# SSTuino_Evo.net
KiCad netlist of a schematic drawn in EAGLE
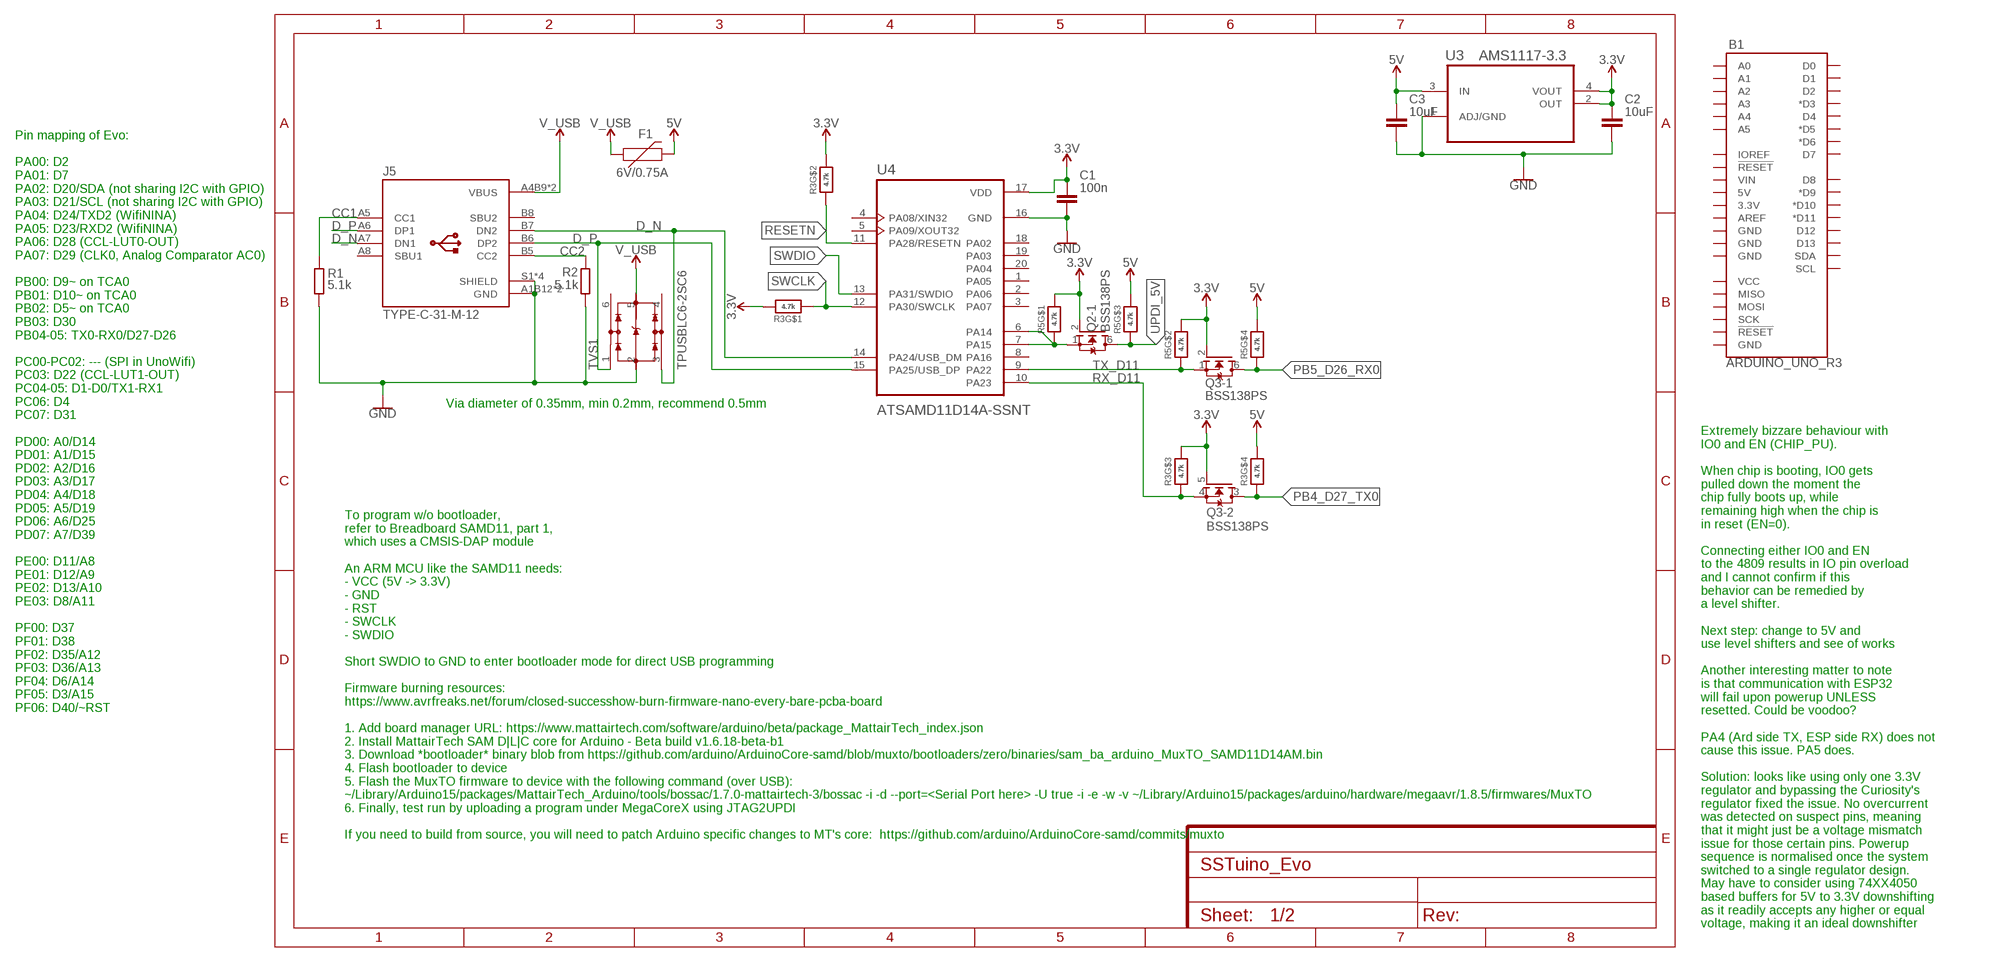
[diagram p0: schematic, sheet 1]
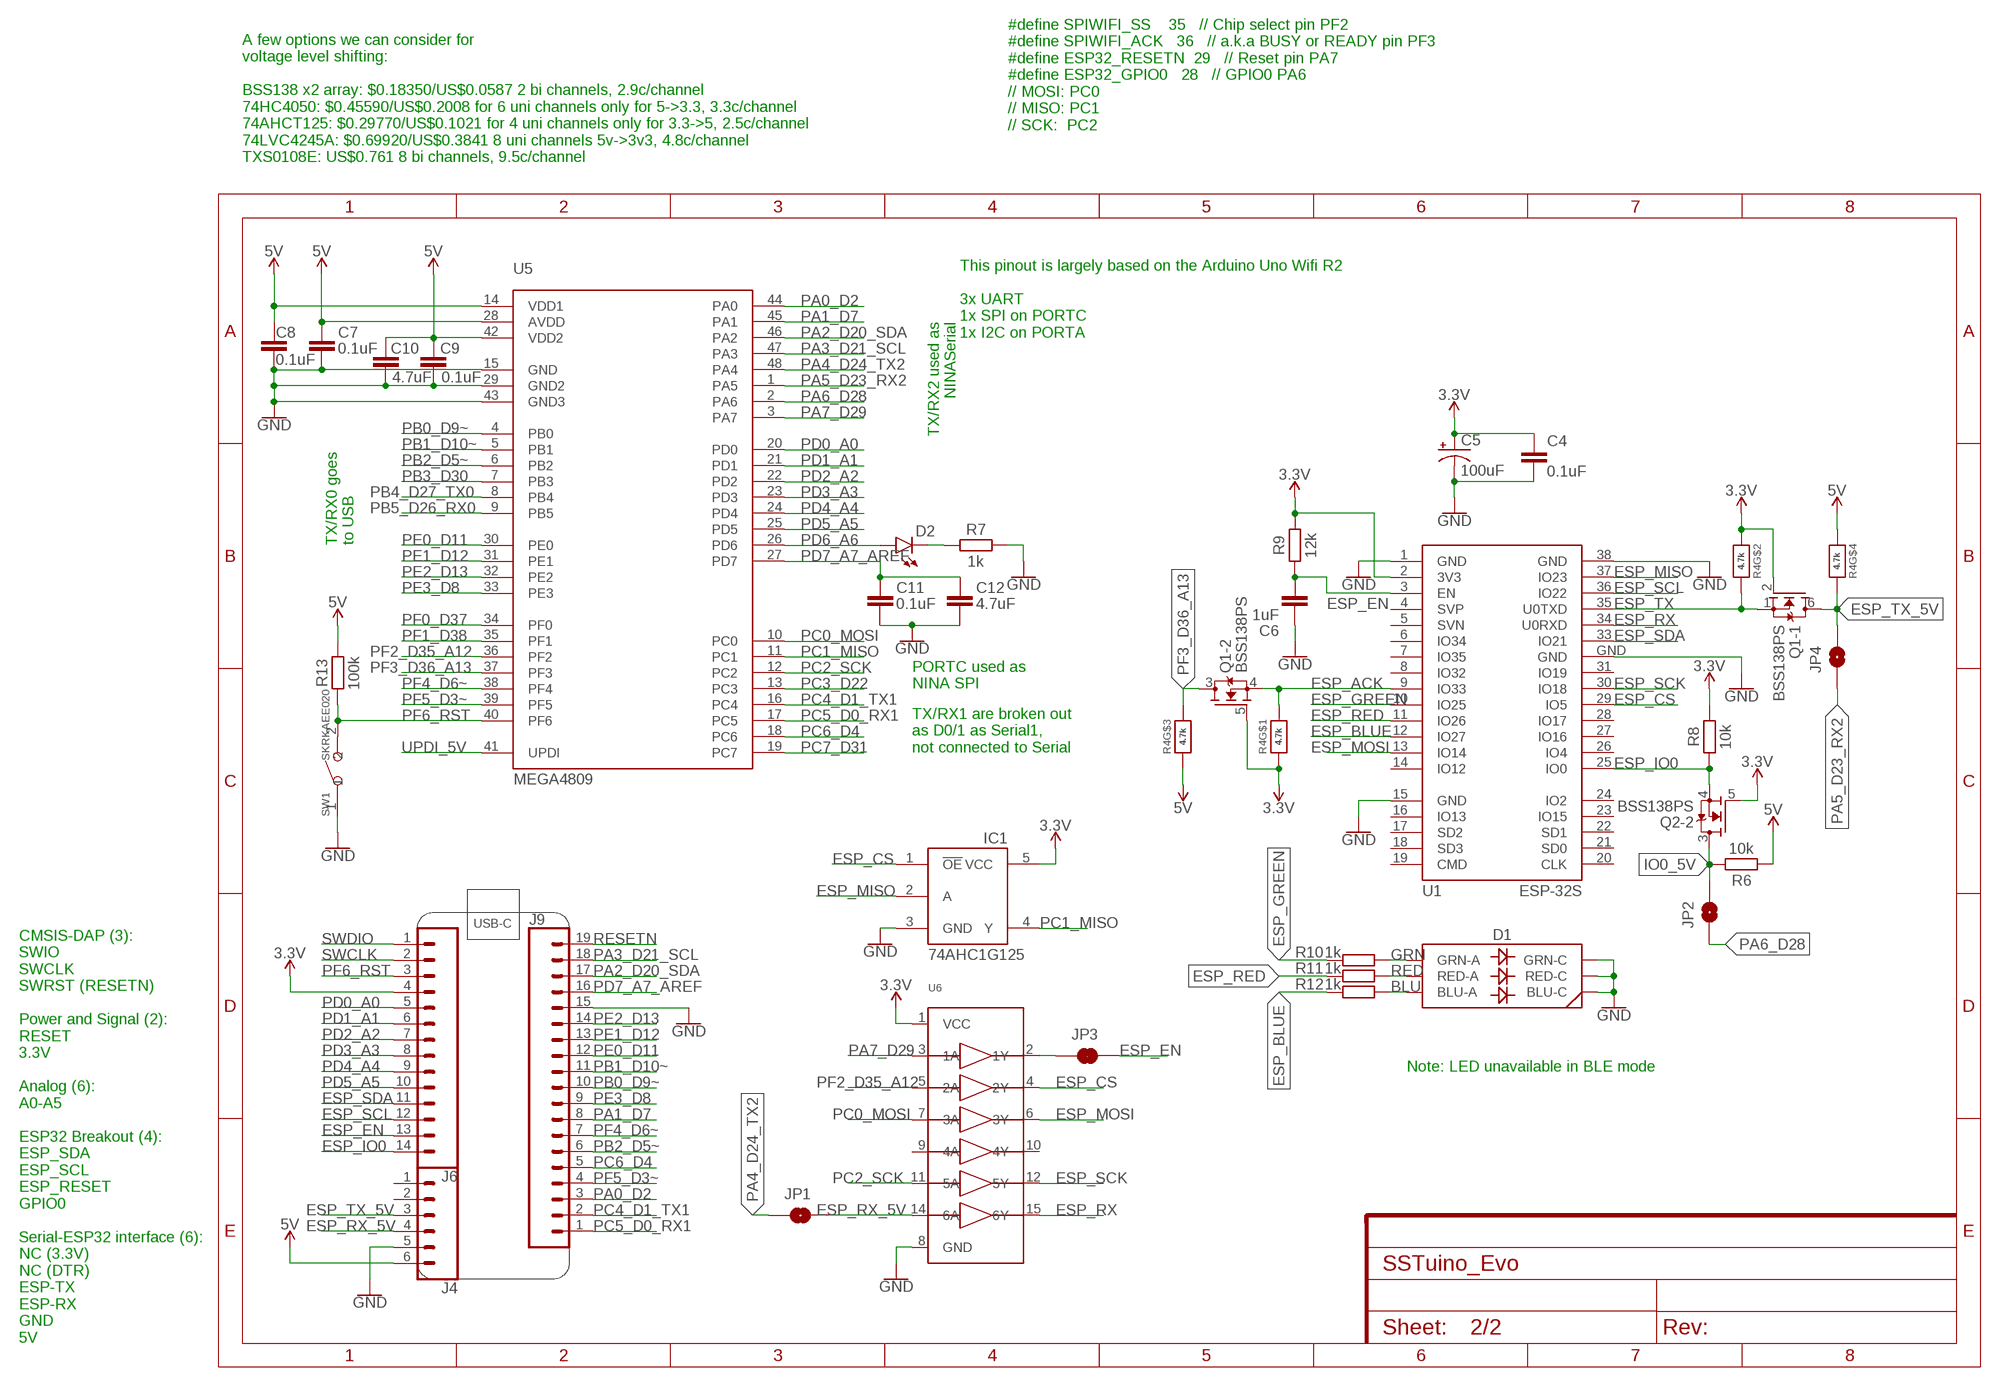
[diagram p1: schematic, sheet 2]

(export (version "E")
  (design (tool "Eeschema 10.0.6"))
  (components
    (comp (ref "B1")
      (value "ARDUINO_UNO_R3")
      (footprint "eagle-import:ARDUINO_R3")
      (libsource (lib "eagle-import") (part "ARDUINO_UNO_R3"))
    )
    (comp (ref "C1")
      (value "100n")
      (footprint "eagle-import:CAPC1005X60")
      (libsource (lib "eagle-import") (part "CCHIP-0402(1005-METRIC)_"))
    )
    (comp (ref "C2")
      (value "10uF")
      (footprint "eagle-import:CAPC1608X85")
      (libsource (lib "eagle-import") (part "CCHIP-0603(1608-METRIC)_"))
    )
    (comp (ref "C3")
      (value "10uF")
      (footprint "eagle-import:CAPC1608X85")
      (libsource (lib "eagle-import") (part "CCHIP-0603(1608-METRIC)_"))
    )
    (comp (ref "F1")
      (value "6V/0.75A")
      (footprint "eagle-import:1206")
      (fields (field (name "LCSC_PART") "C99563"))
      (libsource (lib "eagle-import") (part "PPTC_THREE-QUARTER-AMP"))
    )
    (comp (ref "J5")
      (value "TYPE-C-31-M-12")
      (footprint "eagle-import:HRO_TYPE-C-31-M-12")
      (fields (field (name "MF") "HRO Electronics Co., Ltd.") (field (name "LCSC_PART") "C165948"))
      (libsource (lib "eagle-import") (part "TYPE-C-31-M-12"))
    )
    (comp (ref "Q2")
      (value "BSS138PS")
      (footprint "eagle-import:ARDUINO-TRANSISTORS_SOT363")
      (fields (field (name "MANUFACTURER") "NXP") (field (name "LCSC_PART") "C193381"))
      (libsource (lib "eagle-import") (part "BSS138PS"))
    )
    (comp (ref "Q3")
      (value "BSS138PS")
      (footprint "eagle-import:ARDUINO-TRANSISTORS_SOT363")
      (fields (field (name "MANUFACTURER") "NXP") (field (name "LCSC_PART") "C193381"))
      (libsource (lib "eagle-import") (part "BSS138PS"))
    )
    (comp (ref "R1")
      (value "5.1k")
      (footprint "eagle-import:RESC1005X40")
      (libsource (lib "eagle-import") (part "RCHIP-0402(1005-METRIC)_"))
    )
    (comp (ref "R2")
      (value "5.1k")
      (footprint "eagle-import:RESC1005X40")
      (libsource (lib "eagle-import") (part "RCHIP-0402(1005-METRIC)_"))
    )
    (comp (ref "R3")
      (value "4.7k")
      (footprint "eagle-import:RESPACK_4X0402")
      (fields (field (name "LCSC_PART") "C1980"))
      (libsource (lib "eagle-import") (part "RESISTOR_4PACK0402"))
    )
    (comp (ref "R5")
      (value "4.7k")
      (footprint "eagle-import:RESPACK_4X0402")
      (fields (field (name "LCSC_PART") "C1980"))
      (libsource (lib "eagle-import") (part "RESISTOR_4PACK0402"))
    )
    (comp (ref "TVS1")
      (value "TPUSBLC6-2SC6")
      (footprint "eagle-import:SOT95P280X110-6N")
      (fields (field (name "LCSC_PART") "C558442"))
      (libsource (lib "eagle-import") (part "TPUSBLC6-2SC6"))
    )
    (comp (ref "U3")
      (value "AMS1117-3.3")
      (footprint "eagle-import:SOT230P696X180-4N")
      (fields (field (name "MPN") "LM1117MP-3.3") (field (name "LCSC_PART") "C6186"))
      (libsource (lib "eagle-import") (part "LM1117MP-3.3"))
    )
    (comp (ref "U4")
      (value "ATSAMD11D14A-SSNT")
      (footprint "eagle-import:SOIC127P1030X265-20N")
      (fields (field (name "MF") "Microchip") (field (name "LCSC_PART") "C2053599"))
      (libsource (lib "eagle-import") (part "ATSAMD11D14A-SSNT"))
    )
    (comp (ref "C4")
      (value "0.1uF")
      (footprint "eagle-import:CAPC1005X60")
      (libsource (lib "eagle-import") (part "CCHIP-0402(1005-METRIC)_"))
    )
    (comp (ref "C5")
      (value "100uF")
      (footprint "eagle-import:CAPMP3216X180N")
      (libsource (lib "eagle-import") (part "C-POL-USTANTALUM-1206(3216-METRIC)_"))
    )
    (comp (ref "C6")
      (value "1uF")
      (footprint "eagle-import:CAPC1005X60")
      (libsource (lib "eagle-import") (part "CCHIP-0402(1005-METRIC)_"))
    )
    (comp (ref "C7")
      (value "0.1uF")
      (footprint "eagle-import:CAPC1005X60")
      (libsource (lib "eagle-import") (part "CCHIP-0402(1005-METRIC)_"))
    )
    (comp (ref "C8")
      (value "0.1uF")
      (footprint "eagle-import:CAPC1005X60")
      (libsource (lib "eagle-import") (part "CCHIP-0402(1005-METRIC)_"))
    )
    (comp (ref "C9")
      (value "0.1uF")
      (footprint "eagle-import:CAPC1005X60")
      (libsource (lib "eagle-import") (part "CCHIP-0402(1005-METRIC)_"))
    )
    (comp (ref "C10")
      (value "4.7uF")
      (footprint "eagle-import:CAPC1005X60")
      (libsource (lib "eagle-import") (part "CCHIP-0402(1005-METRIC)_"))
    )
    (comp (ref "C11")
      (value "0.1uF")
      (footprint "eagle-import:CAPC1005X60")
      (libsource (lib "eagle-import") (part "CCHIP-0402(1005-METRIC)_"))
    )
    (comp (ref "C12")
      (value "4.7uF")
      (footprint "eagle-import:CAPC1005X60")
      (libsource (lib "eagle-import") (part "CCHIP-0402(1005-METRIC)_"))
    )
    (comp (ref "D1")
      (value "LED-RGBTC5050RGBF08")
      (footprint "eagle-import:LED-TRICOLOR-5050")
      (libsource (lib "eagle-import") (part "LED-RGBTC5050RGBF08"))
    )
    (comp (ref "D2")
      (value "LED0603")
      (footprint "eagle-import:LED-0603")
      (libsource (lib "eagle-import") (part "LED0603"))
    )
    (comp (ref "IC1")
      (value "74AHC1G125")
      (footprint "eagle-import:SOT23-5L")
      (fields (field (name "LCSC_PART") "C124295"))
      (libsource (lib "eagle-import") (part "74AHC1G125"))
    )
    (comp (ref "J4")
      (value "CONN_06NO_SILK_FEMALE_PTH")
      (footprint "eagle-import:1X06_NO_SILK")
      (libsource (lib "eagle-import") (part "CONN_06NO_SILK_FEMALE_PTH"))
    )
    (comp (ref "J6")
      (value "CONN_14NO_SILK")
      (footprint "eagle-import:1X14_NO_SILK")
      (libsource (lib "eagle-import") (part "CONN_14NO_SILK"))
    )
    (comp (ref "J9")
      (value "CONN_191X19_NO_SILK")
      (footprint "eagle-import:1X19_NO_SILK")
      (libsource (lib "eagle-import") (part "CONN_191X19_NO_SILK"))
    )
    (comp (ref "JP1")
      (value "JUMPER-SMT_2_NO_SILK")
      (footprint "eagle-import:SMT-JUMPER_2_NO_SILK")
      (libsource (lib "eagle-import") (part "JUMPER-SMT_2_NO_SILK"))
    )
    (comp (ref "JP2")
      (value "JUMPER-SMT_2_NO_SILK")
      (footprint "eagle-import:SMT-JUMPER_2_NO_SILK")
      (libsource (lib "eagle-import") (part "JUMPER-SMT_2_NO_SILK"))
    )
    (comp (ref "JP3")
      (value "JUMPER-SMT_2_NC_TRACE_SILK")
      (footprint "eagle-import:SMT-JUMPER_2_NC_TRACE_SILK")
      (libsource (lib "eagle-import") (part "JUMPER-SMT_2_NC_TRACE_SILK"))
    )
    (comp (ref "JP4")
      (value "JUMPER-SMT_2_NO_SILK")
      (footprint "eagle-import:SMT-JUMPER_2_NO_SILK")
      (libsource (lib "eagle-import") (part "JUMPER-SMT_2_NO_SILK"))
    )
    (comp (ref "Q1")
      (value "BSS138PS")
      (footprint "eagle-import:ARDUINO-TRANSISTORS_SOT363")
      (fields (field (name "MANUFACTURER") "NXP") (field (name "LCSC_PART") "C193381"))
      (libsource (lib "eagle-import") (part "BSS138PS"))
    )
    (comp (ref "R4")
      (value "4.7k")
      (footprint "eagle-import:RESPACK_4X0402")
      (fields (field (name "LCSC_PART") "C1980"))
      (libsource (lib "eagle-import") (part "RESISTOR_4PACK0402"))
    )
    (comp (ref "R6")
      (value "10k")
      (footprint "eagle-import:RESC1005X40")
      (libsource (lib "eagle-import") (part "RCHIP-0402(1005-METRIC)_"))
    )
    (comp (ref "R7")
      (value "1k")
      (footprint "eagle-import:RESC1005X40")
      (libsource (lib "eagle-import") (part "RCHIP-0402(1005-METRIC)_"))
    )
    (comp (ref "R8")
      (value "10k")
      (footprint "eagle-import:RESC1005X40")
      (libsource (lib "eagle-import") (part "RCHIP-0402(1005-METRIC)_"))
    )
    (comp (ref "R9")
      (value "12k")
      (footprint "eagle-import:RESC1005X40")
      (libsource (lib "eagle-import") (part "RCHIP-0402(1005-METRIC)_"))
    )
    (comp (ref "R10")
      (value "1k")
      (footprint "eagle-import:RESC1005X40")
      (libsource (lib "eagle-import") (part "RCHIP-0402(1005-METRIC)_"))
    )
    (comp (ref "R11")
      (value "1k")
      (footprint "eagle-import:RESC1005X40")
      (libsource (lib "eagle-import") (part "RCHIP-0402(1005-METRIC)_"))
    )
    (comp (ref "R12")
      (value "1k")
      (footprint "eagle-import:RESC1005X40")
      (libsource (lib "eagle-import") (part "RCHIP-0402(1005-METRIC)_"))
    )
    (comp (ref "R13")
      (value "100k")
      (footprint "eagle-import:RESC1005X40")
      (libsource (lib "eagle-import") (part "RCHIP-0402(1005-METRIC)_"))
    )
    (comp (ref "SW1")
      (value "SKRKAEE020")
      (footprint "eagle-import:SW2-2.6-3.9X2.9X1.5+0.4MM")
      (fields (field (name "LCSC_PART") "C115357") (field (name "LCSC_PART_1") "C115357"))
      (libsource (lib "eagle-import") (part "SMD-BUTTON(2P-3.9X2.9X1.5+0.4MM)-SKRKAEE020"))
    )
    (comp (ref "U1")
      (value "ESP-32S")
      (footprint "eagle-import:ESP-32S")
      (libsource (lib "eagle-import") (part "ESP-32S"))
    )
    (comp (ref "U5")
      (value "MEGA4809")
      (footprint "eagle-import:TQFP48")
      (fields (field (name "LCSC_PART") "C189475"))
      (libsource (lib "eagle-import") (part "MEGA4809"))
    )
    (comp (ref "U6")
      (value "74HC4050DTSSOP")
      (footprint "eagle-import:TSSOP16")
      (fields (field (name "LCSC_PART") "C43181"))
      (libsource (lib "eagle-import") (part "74HC4050DTSSOP"))
    )
  )
  (nets
    (net (code "1") (name "3.3V") (class "Default")
      (node (ref "C1") (pin "1") (pinfunction "1_1") (pintype "passive"))
      (node (ref "C2") (pin "1") (pinfunction "1_1") (pintype "passive"))
      (node (ref "C4") (pin "1") (pinfunction "1_1") (pintype "passive"))
      (node (ref "C5") (pin "1") (pinfunction "+_1") (pintype "passive"))
      (node (ref "IC1") (pin "5") (pinfunction "VCC_5") (pintype "power_in"))
      (node (ref "J6") (pin "4") (pinfunction "4_4") (pintype "passive"))
      (node (ref "Q1") (pin "2") (pinfunction "G_2") (pintype "passive"))
      (node (ref "Q1") (pin "5") (pinfunction "G_5") (pintype "passive"))
      (node (ref "Q2") (pin "2") (pinfunction "G_2") (pintype "passive"))
      (node (ref "Q2") (pin "5") (pinfunction "G_5") (pintype "passive"))
      (node (ref "Q3") (pin "2") (pinfunction "G_2") (pintype "passive"))
      (node (ref "Q3") (pin "5") (pinfunction "G_5") (pintype "passive"))
      (node (ref "R3") (pin "6") (pinfunction "2_6") (pintype "passive"))
      (node (ref "R3") (pin "7") (pinfunction "2_7") (pintype "passive"))
      (node (ref "R3") (pin "8") (pinfunction "2_8") (pintype "passive"))
      (node (ref "R4") (pin "1") (pinfunction "1_1") (pintype "passive"))
      (node (ref "R4") (pin "2") (pinfunction "1_2") (pintype "passive"))
      (node (ref "R5") (pin "7") (pinfunction "2_7") (pintype "passive"))
      (node (ref "R5") (pin "8") (pinfunction "2_8") (pintype "passive"))
      (node (ref "R8") (pin "2") (pinfunction "2_2") (pintype "passive"))
      (node (ref "R9") (pin "2") (pinfunction "2_2") (pintype "passive"))
      (node (ref "U1") (pin "2") (pinfunction "3V3_2") (pintype "power_in"))
      (node (ref "U3") (pin "2") (pinfunction "OUT_2") (pintype "output"))
      (node (ref "U3") (pin "4") (pinfunction "VOUT_4") (pintype "output"))
      (node (ref "U4") (pin "17") (pinfunction "VDD_17") (pintype "power_in"))
      (node (ref "U6") (pin "1") (pinfunction "VCC_1") (pintype "bidirectional"))
    )
    (net (code "2") (name "5V") (class "Default")
      (node (ref "C10") (pin "1") (pinfunction "1_1") (pintype "passive"))
      (node (ref "C3") (pin "1") (pinfunction "1_1") (pintype "passive"))
      (node (ref "C7") (pin "1") (pinfunction "1_1") (pintype "passive"))
      (node (ref "C8") (pin "1") (pinfunction "1_1") (pintype "passive"))
      (node (ref "C9") (pin "1") (pinfunction "1_1") (pintype "passive"))
      (node (ref "F1") (pin "2") (pinfunction "2_2") (pintype "bidirectional"))
      (node (ref "J4") (pin "6") (pinfunction "6_6") (pintype "passive"))
      (node (ref "R13") (pin "2") (pinfunction "2_2") (pintype "passive"))
      (node (ref "R3") (pin "5") (pinfunction "2_5") (pintype "passive"))
      (node (ref "R4") (pin "3") (pinfunction "1_3") (pintype "passive"))
      (node (ref "R4") (pin "4") (pinfunction "1_4") (pintype "passive"))
      (node (ref "R5") (pin "5") (pinfunction "2_5") (pintype "passive"))
      (node (ref "R5") (pin "6") (pinfunction "2_6") (pintype "passive"))
      (node (ref "R6") (pin "1") (pinfunction "1_1") (pintype "passive"))
      (node (ref "U3") (pin "3") (pinfunction "IN_3") (pintype "input"))
      (node (ref "U5") (pin "14") (pinfunction "VDD1_14") (pintype "bidirectional"))
      (node (ref "U5") (pin "28") (pinfunction "AVDD_28") (pintype "bidirectional"))
      (node (ref "U5") (pin "42") (pinfunction "VDD2_42") (pintype "bidirectional"))
    )
    (net (code "3") (name "BLU") (class "Default")
      (node (ref "D1") (pin "6") (pinfunction "BLU-A_6") (pintype "bidirectional"))
      (node (ref "R12") (pin "2") (pinfunction "2_2") (pintype "passive"))
    )
    (net (code "4") (name "CC1") (class "Default")
      (node (ref "J5") (pin "A5") (pinfunction "CC1_A5") (pintype "bidirectional"))
      (node (ref "R1") (pin "1") (pinfunction "1_1") (pintype "passive"))
    )
    (net (code "5") (name "CC2") (class "Default")
      (node (ref "J5") (pin "B5") (pinfunction "CC2_B5") (pintype "bidirectional"))
      (node (ref "R2") (pin "2") (pinfunction "2_2") (pintype "passive"))
    )
    (net (code "6") (name "D_N") (class "Default")
      (node (ref "J5") (pin "A7") (pinfunction "DN1_A7") (pintype "bidirectional"))
      (node (ref "J5") (pin "B7") (pinfunction "DN2_B7") (pintype "bidirectional"))
      (node (ref "TVS1") (pin "3") (pinfunction "IO2_3") (pintype "passive"))
      (node (ref "U4") (pin "14") (pinfunction "PA24/USB_DM_14") (pintype "bidirectional"))
    )
    (net (code "7") (name "D_P") (class "Default")
      (node (ref "J5") (pin "A6") (pinfunction "DP1_A6") (pintype "bidirectional"))
      (node (ref "J5") (pin "B6") (pinfunction "DP2_B6") (pintype "bidirectional"))
      (node (ref "TVS1") (pin "1") (pinfunction "IO1_1") (pintype "passive"))
      (node (ref "U4") (pin "15") (pinfunction "PA25/USB_DP_15") (pintype "bidirectional"))
    )
    (net (code "8") (name "ESP_ACK") (class "Default")
      (node (ref "Q1") (pin "4") (pinfunction "S_4") (pintype "passive"))
      (node (ref "R4") (pin "8") (pinfunction "2_8") (pintype "passive"))
      (node (ref "U1") (pin "9") (pinfunction "IO33_9") (pintype "bidirectional"))
    )
    (net (code "9") (name "ESP_BLUE") (class "Default")
      (node (ref "R12") (pin "1") (pinfunction "1_1") (pintype "passive"))
      (node (ref "U1") (pin "12") (pinfunction "IO27_12") (pintype "bidirectional"))
    )
    (net (code "10") (name "ESP_CS") (class "Default")
      (node (ref "IC1") (pin "1") (pinfunction "~{OE}_1") (pintype "input"))
      (node (ref "U1") (pin "29") (pinfunction "IO5_29") (pintype "bidirectional"))
      (node (ref "U6") (pin "4") (pinfunction "2Y_4") (pintype "bidirectional"))
    )
    (net (code "11") (name "ESP_EN") (class "Default")
      (node (ref "C6") (pin "2") (pinfunction "2_2") (pintype "passive"))
      (node (ref "J6") (pin "13") (pinfunction "13_13") (pintype "passive"))
      (node (ref "JP3") (pin "2") (pinfunction "2_2") (pintype "passive"))
      (node (ref "R9") (pin "1") (pinfunction "1_1") (pintype "passive"))
      (node (ref "U1") (pin "3") (pinfunction "EN_3") (pintype "input"))
    )
    (net (code "12") (name "ESP_GREEN") (class "Default")
      (node (ref "R10") (pin "1") (pinfunction "1_1") (pintype "passive"))
      (node (ref "U1") (pin "10") (pinfunction "IO25_10") (pintype "bidirectional"))
    )
    (net (code "13") (name "ESP_IO0") (class "Default")
      (node (ref "J6") (pin "14") (pinfunction "14_14") (pintype "passive"))
      (node (ref "Q2") (pin "4") (pinfunction "S_4") (pintype "passive"))
      (node (ref "R8") (pin "1") (pinfunction "1_1") (pintype "passive"))
      (node (ref "U1") (pin "25") (pinfunction "IO0_25") (pintype "bidirectional"))
    )
    (net (code "14") (name "ESP_MISO") (class "Default")
      (node (ref "IC1") (pin "2") (pinfunction "A_2") (pintype "input"))
      (node (ref "U1") (pin "37") (pinfunction "IO23_37") (pintype "bidirectional"))
    )
    (net (code "15") (name "ESP_MOSI") (class "Default")
      (node (ref "U1") (pin "13") (pinfunction "IO14_13") (pintype "bidirectional"))
      (node (ref "U6") (pin "6") (pinfunction "3Y_6") (pintype "bidirectional"))
    )
    (net (code "16") (name "ESP_RED") (class "Default")
      (node (ref "R11") (pin "1") (pinfunction "1_1") (pintype "passive"))
      (node (ref "U1") (pin "11") (pinfunction "IO26_11") (pintype "bidirectional"))
    )
    (net (code "17") (name "ESP_RX") (class "Default")
      (node (ref "U1") (pin "34") (pinfunction "U0RXD_34") (pintype "bidirectional"))
      (node (ref "U6") (pin "15") (pinfunction "6Y_15") (pintype "bidirectional"))
    )
    (net (code "18") (name "ESP_RX_5V") (class "Default")
      (node (ref "J4") (pin "4") (pinfunction "4_4") (pintype "passive"))
      (node (ref "JP1") (pin "2") (pinfunction "2_2") (pintype "passive"))
      (node (ref "U6") (pin "14") (pinfunction "6A_14") (pintype "bidirectional"))
    )
    (net (code "19") (name "ESP_SCK") (class "Default")
      (node (ref "U1") (pin "30") (pinfunction "IO18_30") (pintype "bidirectional"))
      (node (ref "U6") (pin "12") (pinfunction "5Y_12") (pintype "bidirectional"))
    )
    (net (code "20") (name "ESP_SCL") (class "Default")
      (node (ref "J6") (pin "12") (pinfunction "12_12") (pintype "passive"))
      (node (ref "U1") (pin "36") (pinfunction "IO22_36") (pintype "bidirectional"))
    )
    (net (code "21") (name "ESP_SDA") (class "Default")
      (node (ref "J6") (pin "11") (pinfunction "11_11") (pintype "passive"))
      (node (ref "U1") (pin "33") (pinfunction "IO21_33") (pintype "bidirectional"))
    )
    (net (code "22") (name "ESP_TX") (class "Default")
      (node (ref "Q1") (pin "1") (pinfunction "S_1") (pintype "passive"))
      (node (ref "R4") (pin "7") (pinfunction "2_7") (pintype "passive"))
      (node (ref "U1") (pin "35") (pinfunction "U0TXD_35") (pintype "bidirectional"))
    )
    (net (code "23") (name "ESP_TX_5V") (class "Default")
      (node (ref "J4") (pin "3") (pinfunction "3_3") (pintype "passive"))
      (node (ref "JP4") (pin "2") (pinfunction "2_2") (pintype "passive"))
      (node (ref "Q1") (pin "6") (pinfunction "D_6") (pintype "passive"))
      (node (ref "R4") (pin "5") (pinfunction "2_5") (pintype "passive"))
    )
    (net (code "24") (name "GND") (class "Default")
      (node (ref "C1") (pin "2") (pinfunction "2_2") (pintype "passive"))
      (node (ref "C10") (pin "2") (pinfunction "2_2") (pintype "passive"))
      (node (ref "C11") (pin "2") (pinfunction "2_2") (pintype "passive"))
      (node (ref "C12") (pin "2") (pinfunction "2_2") (pintype "passive"))
      (node (ref "C2") (pin "2") (pinfunction "2_2") (pintype "passive"))
      (node (ref "C3") (pin "2") (pinfunction "2_2") (pintype "passive"))
      (node (ref "C4") (pin "2") (pinfunction "2_2") (pintype "passive"))
      (node (ref "C5") (pin "2") (pinfunction "-_2") (pintype "passive"))
      (node (ref "C6") (pin "1") (pinfunction "1_1") (pintype "passive"))
      (node (ref "C7") (pin "2") (pinfunction "2_2") (pintype "passive"))
      (node (ref "C8") (pin "2") (pinfunction "2_2") (pintype "passive"))
      (node (ref "C9") (pin "2") (pinfunction "2_2") (pintype "passive"))
      (node (ref "D1") (pin "1") (pinfunction "BLU-C_1") (pintype "bidirectional"))
      (node (ref "D1") (pin "2") (pinfunction "RED-C_2") (pintype "bidirectional"))
      (node (ref "D1") (pin "3") (pinfunction "GRN-C_3") (pintype "bidirectional"))
      (node (ref "IC1") (pin "3") (pinfunction "GND_3") (pintype "power_in"))
      (node (ref "J4") (pin "5") (pinfunction "5_5") (pintype "passive"))
      (node (ref "J5") (pin "A1B12") (pinfunction "GND_A1B12") (pintype "power_in"))
      (node (ref "J5") (pin "B1A12") (pinfunction "GND_B1A12") (pintype "power_in"))
      (node (ref "J5") (pin "S1") (pinfunction "SHIELD_S1") (pintype "passive"))
      (node (ref "J5") (pin "S2") (pinfunction "SHIELD_S2") (pintype "passive"))
      (node (ref "J5") (pin "S3") (pinfunction "SHIELD_S3") (pintype "passive"))
      (node (ref "J5") (pin "S4") (pinfunction "SHIELD_S4") (pintype "passive"))
      (node (ref "J9") (pin "15") (pinfunction "15_15") (pintype "passive"))
      (node (ref "R1") (pin "2") (pinfunction "2_2") (pintype "passive"))
      (node (ref "R2") (pin "1") (pinfunction "1_1") (pintype "passive"))
      (node (ref "R7") (pin "2") (pinfunction "2_2") (pintype "passive"))
      (node (ref "SW1") (pin "1") (pinfunction "1_1") (pintype "bidirectional"))
      (node (ref "TVS1") (pin "2") (pinfunction "VSS_2") (pintype "power_in"))
      (node (ref "U1") (pin "1") (pinfunction "GND_1") (pintype "power_in"))
      (node (ref "U1") (pin "15") (pinfunction "GND_15") (pintype "power_in"))
      (node (ref "U1") (pin "38") (pinfunction "GND_38") (pintype "power_in"))
      (node (ref "U1") (pin "GND") (pinfunction "GND_GND") (pintype "power_in"))
      (node (ref "U3") (pin "1") (pinfunction "ADJ/GND_1") (pintype "passive"))
      (node (ref "U4") (pin "16") (pinfunction "GND_16") (pintype "power_in"))
      (node (ref "U5") (pin "15") (pinfunction "GND_15") (pintype "bidirectional"))
      (node (ref "U5") (pin "29") (pinfunction "GND2_29") (pintype "bidirectional"))
      (node (ref "U5") (pin "43") (pinfunction "GND3_43") (pintype "bidirectional"))
      (node (ref "U6") (pin "8") (pinfunction "GND_8") (pintype "bidirectional"))
    )
    (net (code "25") (name "GRN") (class "Default")
      (node (ref "D1") (pin "4") (pinfunction "GRN-A_4") (pintype "bidirectional"))
      (node (ref "R10") (pin "2") (pinfunction "2_2") (pintype "passive"))
    )
    (net (code "26") (name "IO0_5V") (class "Default")
      (node (ref "JP2") (pin "2") (pinfunction "2_2") (pintype "passive"))
      (node (ref "Q2") (pin "3") (pinfunction "D_3") (pintype "passive"))
      (node (ref "R6") (pin "2") (pinfunction "2_2") (pintype "passive"))
    )
    (net (code "27") (name "Net-(D2-PadC)") (class "Default")
      (node (ref "D2") (pin "C") (pinfunction "C_C") (pintype "passive"))
      (node (ref "R7") (pin "1") (pinfunction "1_1") (pintype "passive"))
    )
    (net (code "28") (name "Net-(Q2A-S)") (class "Default")
      (node (ref "Q2") (pin "1") (pinfunction "S_1") (pintype "passive"))
      (node (ref "R5") (pin "1") (pinfunction "1_1") (pintype "passive"))
      (node (ref "U4") (pin "6") (pinfunction "PA14_6") (pintype "bidirectional"))
      (node (ref "U4") (pin "7") (pinfunction "PA15_7") (pintype "bidirectional"))
    )
    (net (code "29") (name "Net-(U6-1Y)") (class "Default")
      (node (ref "JP3") (pin "1") (pinfunction "1_1") (pintype "passive"))
      (node (ref "U6") (pin "2") (pinfunction "1Y_2") (pintype "bidirectional"))
    )
    (net (code "30") (name "PA0_D2") (class "Default")
      (node (ref "J9") (pin "3") (pinfunction "3_3") (pintype "passive"))
      (node (ref "U5") (pin "44") (pinfunction "PA0_44") (pintype "bidirectional"))
    )
    (net (code "31") (name "PA1_D7") (class "Default")
      (node (ref "J9") (pin "8") (pinfunction "8_8") (pintype "passive"))
      (node (ref "U5") (pin "45") (pinfunction "PA1_45") (pintype "bidirectional"))
    )
    (net (code "32") (name "PA2_D20_SDA") (class "Default")
      (node (ref "J9") (pin "17") (pinfunction "17_17") (pintype "passive"))
      (node (ref "U5") (pin "46") (pinfunction "PA2_46") (pintype "bidirectional"))
    )
    (net (code "33") (name "PA3_D21_SCL") (class "Default")
      (node (ref "J9") (pin "18") (pinfunction "18_18") (pintype "passive"))
      (node (ref "U5") (pin "47") (pinfunction "PA3_47") (pintype "bidirectional"))
    )
    (net (code "34") (name "PA4_D24_TX2") (class "Default")
      (node (ref "JP1") (pin "1") (pinfunction "1_1") (pintype "passive"))
      (node (ref "U5") (pin "48") (pinfunction "PA4_48") (pintype "bidirectional"))
    )
    (net (code "35") (name "PA5_D23_RX2") (class "Default")
      (node (ref "JP4") (pin "1") (pinfunction "1_1") (pintype "passive"))
      (node (ref "U5") (pin "1") (pinfunction "PA5_1") (pintype "bidirectional"))
    )
    (net (code "36") (name "PA6_D28") (class "Default")
      (node (ref "JP2") (pin "1") (pinfunction "1_1") (pintype "passive"))
      (node (ref "U5") (pin "2") (pinfunction "PA6_2") (pintype "bidirectional"))
    )
    (net (code "37") (name "PA7_D29") (class "Default")
      (node (ref "U5") (pin "3") (pinfunction "PA7_3") (pintype "bidirectional"))
      (node (ref "U6") (pin "3") (pinfunction "1A_3") (pintype "bidirectional"))
    )
    (net (code "38") (name "PB0_D9~{}") (class "Default")
      (node (ref "J9") (pin "10") (pinfunction "10_10") (pintype "passive"))
      (node (ref "U5") (pin "4") (pinfunction "PB0_4") (pintype "bidirectional"))
    )
    (net (code "39") (name "PB1_D10~{}") (class "Default")
      (node (ref "J9") (pin "11") (pinfunction "11_11") (pintype "passive"))
      (node (ref "U5") (pin "5") (pinfunction "PB1_5") (pintype "bidirectional"))
    )
    (net (code "40") (name "PB2_D5~{}") (class "Default")
      (node (ref "J9") (pin "6") (pinfunction "6_6") (pintype "passive"))
      (node (ref "U5") (pin "6") (pinfunction "PB2_6") (pintype "bidirectional"))
    )
    (net (code "41") (name "PB3_D30") (class "Default")
      (node (ref "U5") (pin "7") (pinfunction "PB3_7") (pintype "bidirectional"))
    )
    (net (code "42") (name "PB4_D27_TX0") (class "Default")
      (node (ref "Q3") (pin "3") (pinfunction "D_3") (pintype "passive"))
      (node (ref "R3") (pin "4") (pinfunction "1_4") (pintype "passive"))
      (node (ref "U5") (pin "8") (pinfunction "PB4_8") (pintype "bidirectional"))
    )
    (net (code "43") (name "PB5_D26_RX0") (class "Default")
      (node (ref "Q3") (pin "6") (pinfunction "D_6") (pintype "passive"))
      (node (ref "R5") (pin "4") (pinfunction "1_4") (pintype "passive"))
      (node (ref "U5") (pin "9") (pinfunction "PB5_9") (pintype "bidirectional"))
    )
    (net (code "44") (name "PC0_MOSI") (class "Default")
      (node (ref "U5") (pin "10") (pinfunction "PC0_10") (pintype "bidirectional"))
      (node (ref "U6") (pin "7") (pinfunction "3A_7") (pintype "bidirectional"))
    )
    (net (code "45") (name "PC1_MISO") (class "Default")
      (node (ref "IC1") (pin "4") (pinfunction "Y_4") (pintype "output"))
      (node (ref "U5") (pin "11") (pinfunction "PC1_11") (pintype "bidirectional"))
    )
    (net (code "46") (name "PC2_SCK") (class "Default")
      (node (ref "U5") (pin "12") (pinfunction "PC2_12") (pintype "bidirectional"))
      (node (ref "U6") (pin "11") (pinfunction "5A_11") (pintype "bidirectional"))
    )
    (net (code "47") (name "PC3_D22") (class "Default")
      (node (ref "U5") (pin "13") (pinfunction "PC3_13") (pintype "bidirectional"))
    )
    (net (code "48") (name "PC4_D1_TX1") (class "Default")
      (node (ref "J9") (pin "2") (pinfunction "2_2") (pintype "passive"))
      (node (ref "U5") (pin "16") (pinfunction "PC4_16") (pintype "bidirectional"))
    )
    (net (code "49") (name "PC5_D0_RX1") (class "Default")
      (node (ref "J9") (pin "1") (pinfunction "1_1") (pintype "passive"))
      (node (ref "U5") (pin "17") (pinfunction "PC5_17") (pintype "bidirectional"))
    )
    (net (code "50") (name "PC6_D4") (class "Default")
      (node (ref "J9") (pin "5") (pinfunction "5_5") (pintype "passive"))
      (node (ref "U5") (pin "18") (pinfunction "PC6_18") (pintype "bidirectional"))
    )
    (net (code "51") (name "PC7_D31") (class "Default")
      (node (ref "U5") (pin "19") (pinfunction "PC7_19") (pintype "bidirectional"))
    )
    (net (code "52") (name "PD0_A0") (class "Default")
      (node (ref "J6") (pin "5") (pinfunction "5_5") (pintype "passive"))
      (node (ref "U5") (pin "20") (pinfunction "PD0_20") (pintype "bidirectional"))
    )
    (net (code "53") (name "PD1_A1") (class "Default")
      (node (ref "J6") (pin "6") (pinfunction "6_6") (pintype "passive"))
      (node (ref "U5") (pin "21") (pinfunction "PD1_21") (pintype "bidirectional"))
    )
    (net (code "54") (name "PD2_A2") (class "Default")
      (node (ref "J6") (pin "7") (pinfunction "7_7") (pintype "passive"))
      (node (ref "U5") (pin "22") (pinfunction "PD2_22") (pintype "bidirectional"))
    )
    (net (code "55") (name "PD3_A3") (class "Default")
      (node (ref "J6") (pin "8") (pinfunction "8_8") (pintype "passive"))
      (node (ref "U5") (pin "23") (pinfunction "PD3_23") (pintype "bidirectional"))
    )
    (net (code "56") (name "PD4_A4") (class "Default")
      (node (ref "J6") (pin "9") (pinfunction "9_9") (pintype "passive"))
      (node (ref "U5") (pin "24") (pinfunction "PD4_24") (pintype "bidirectional"))
    )
    (net (code "57") (name "PD5_A5") (class "Default")
      (node (ref "J6") (pin "10") (pinfunction "10_10") (pintype "passive"))
      (node (ref "U5") (pin "25") (pinfunction "PD5_25") (pintype "bidirectional"))
    )
    (net (code "58") (name "PD6_A6") (class "Default")
      (node (ref "D2") (pin "A") (pinfunction "A_A") (pintype "passive"))
      (node (ref "U5") (pin "26") (pinfunction "PD6_26") (pintype "bidirectional"))
    )
    (net (code "59") (name "PD7_A7_AREF") (class "Default")
      (node (ref "C11") (pin "1") (pinfunction "1_1") (pintype "passive"))
      (node (ref "C12") (pin "1") (pinfunction "1_1") (pintype "passive"))
      (node (ref "J9") (pin "16") (pinfunction "16_16") (pintype "passive"))
      (node (ref "U5") (pin "27") (pinfunction "PD7_27") (pintype "bidirectional"))
    )
    (net (code "60") (name "PE0_D11") (class "Default")
      (node (ref "J9") (pin "12") (pinfunction "12_12") (pintype "passive"))
      (node (ref "U5") (pin "30") (pinfunction "PE0_30") (pintype "bidirectional"))
    )
    (net (code "61") (name "PE1_D12") (class "Default")
      (node (ref "J9") (pin "13") (pinfunction "13_13") (pintype "passive"))
      (node (ref "U5") (pin "31") (pinfunction "PE1_31") (pintype "bidirectional"))
    )
    (net (code "62") (name "PE2_D13") (class "Default")
      (node (ref "J9") (pin "14") (pinfunction "14_14") (pintype "passive"))
      (node (ref "U5") (pin "32") (pinfunction "PE2_32") (pintype "bidirectional"))
    )
    (net (code "63") (name "PE3_D8") (class "Default")
      (node (ref "J9") (pin "9") (pinfunction "9_9") (pintype "passive"))
      (node (ref "U5") (pin "33") (pinfunction "PE3_33") (pintype "bidirectional"))
    )
    (net (code "64") (name "PF0_D37") (class "Default")
      (node (ref "U5") (pin "34") (pinfunction "PF0_34") (pintype "bidirectional"))
    )
    (net (code "65") (name "PF1_D38") (class "Default")
      (node (ref "U5") (pin "35") (pinfunction "PF1_35") (pintype "bidirectional"))
    )
    (net (code "66") (name "PF2_D35_A12") (class "Default")
      (node (ref "U5") (pin "36") (pinfunction "PF2_36") (pintype "bidirectional"))
      (node (ref "U6") (pin "5") (pinfunction "2A_5") (pintype "bidirectional"))
    )
    (net (code "67") (name "PF3_D36_A13") (class "Default")
      (node (ref "Q1") (pin "3") (pinfunction "D_3") (pintype "passive"))
      (node (ref "R4") (pin "6") (pinfunction "2_6") (pintype "passive"))
      (node (ref "U5") (pin "37") (pinfunction "PF3_37") (pintype "bidirectional"))
    )
    (net (code "68") (name "PF4_D6~{}") (class "Default")
      (node (ref "J9") (pin "7") (pinfunction "7_7") (pintype "passive"))
      (node (ref "U5") (pin "38") (pinfunction "PF4_38") (pintype "bidirectional"))
    )
    (net (code "69") (name "PF5_D3~{}") (class "Default")
      (node (ref "J9") (pin "4") (pinfunction "4_4") (pintype "passive"))
      (node (ref "U5") (pin "39") (pinfunction "PF5_39") (pintype "bidirectional"))
    )
    (net (code "70") (name "PF6_RST") (class "Default")
      (node (ref "J6") (pin "3") (pinfunction "3_3") (pintype "passive"))
      (node (ref "R13") (pin "1") (pinfunction "1_1") (pintype "passive"))
      (node (ref "SW1") (pin "2") (pinfunction "2_2") (pintype "bidirectional"))
      (node (ref "U5") (pin "40") (pinfunction "PF6_40") (pintype "bidirectional"))
    )
    (net (code "71") (name "RED") (class "Default")
      (node (ref "D1") (pin "5") (pinfunction "RED-A_5") (pintype "bidirectional"))
      (node (ref "R11") (pin "2") (pinfunction "2_2") (pintype "passive"))
    )
    (net (code "72") (name "RESETN") (class "Default")
      (node (ref "J9") (pin "19") (pinfunction "19_19") (pintype "passive"))
      (node (ref "R3") (pin "2") (pinfunction "1_2") (pintype "passive"))
      (node (ref "U4") (pin "11") (pinfunction "PA28/RESETN_11") (pintype "input"))
    )
    (net (code "73") (name "RX_D11") (class "Default")
      (node (ref "Q3") (pin "4") (pinfunction "S_4") (pintype "passive"))
      (node (ref "R3") (pin "3") (pinfunction "1_3") (pintype "passive"))
      (node (ref "U4") (pin "10") (pinfunction "PA23_10") (pintype "bidirectional"))
    )
    (net (code "74") (name "SWCLK") (class "Default")
      (node (ref "J6") (pin "2") (pinfunction "2_2") (pintype "passive"))
      (node (ref "R3") (pin "1") (pinfunction "1_1") (pintype "passive"))
      (node (ref "U4") (pin "12") (pinfunction "PA30/SWCLK_12") (pintype "bidirectional"))
    )
    (net (code "75") (name "SWDIO") (class "Default")
      (node (ref "J6") (pin "1") (pinfunction "1_1") (pintype "passive"))
      (node (ref "U4") (pin "13") (pinfunction "PA31/SWDIO_13") (pintype "bidirectional"))
    )
    (net (code "76") (name "TX_D11") (class "Default")
      (node (ref "Q3") (pin "1") (pinfunction "S_1") (pintype "passive"))
      (node (ref "R5") (pin "2") (pinfunction "1_2") (pintype "passive"))
      (node (ref "U4") (pin "9") (pinfunction "PA22_9") (pintype "bidirectional"))
    )
    (net (code "77") (name "UPDI_5V") (class "Default")
      (node (ref "Q2") (pin "6") (pinfunction "D_6") (pintype "passive"))
      (node (ref "R5") (pin "3") (pinfunction "1_3") (pintype "passive"))
      (node (ref "U5") (pin "41") (pinfunction "UPDI_41") (pintype "bidirectional"))
    )
    (net (code "78") (name "V_USB") (class "Default")
      (node (ref "F1") (pin "1") (pinfunction "1_1") (pintype "bidirectional"))
      (node (ref "J5") (pin "A4B9") (pinfunction "VBUS_A4B9") (pintype "power_in"))
      (node (ref "J5") (pin "B4A9") (pinfunction "VBUS_B4A9") (pintype "power_in"))
      (node (ref "TVS1") (pin "5") (pinfunction "VCC_5") (pintype "power_in"))
    )
    (net (code "79") (name "unconnected-(B1-*D3-PadD3)") (class "Default")
      (node (ref "B1") (pin "D3") (pinfunction "*D3_D3") (pintype "bidirectional"))
    )
    (net (code "80") (name "unconnected-(B1-*D5-PadD5)") (class "Default")
      (node (ref "B1") (pin "D5") (pinfunction "*D5_D5") (pintype "bidirectional"))
    )
    (net (code "81") (name "unconnected-(B1-*D6-PadD6)") (class "Default")
      (node (ref "B1") (pin "D6") (pinfunction "*D6_D6") (pintype "bidirectional"))
    )
    (net (code "82") (name "unconnected-(B1-*D9-PadD9)") (class "Default")
      (node (ref "B1") (pin "D9") (pinfunction "*D9_D9") (pintype "bidirectional"))
    )
    (net (code "83") (name "unconnected-(B1-*D10-PadD10)") (class "Default")
      (node (ref "B1") (pin "D10") (pinfunction "*D10_D10") (pintype "bidirectional"))
    )
    (net (code "84") (name "unconnected-(B1-*D11-PadD11)") (class "Default")
      (node (ref "B1") (pin "D11") (pinfunction "*D11_D11") (pintype "bidirectional"))
    )
    (net (code "85") (name "unconnected-(B1-GND-PadGND@1)") (class "Default")
      (node (ref "B1") (pin "GND@1") (pinfunction "GND_GND@1") (pintype "bidirectional"))
    )
    (net (code "86") (name "unconnected-(B1-GND-PadGND@2)") (class "Default")
      (node (ref "B1") (pin "GND@2") (pinfunction "GND_GND@2") (pintype "bidirectional"))
    )
    (net (code "87") (name "unconnected-(B1-GND-PadGND@3)") (class "Default")
      (node (ref "B1") (pin "GND@3") (pinfunction "GND_GND@3") (pintype "bidirectional"))
    )
    (net (code "88") (name "unconnected-(B1-GND-PadGND@4)") (class "Default")
      (node (ref "B1") (pin "GND@4") (pinfunction "GND_GND@4") (pintype "bidirectional"))
    )
    (net (code "89") (name "unconnected-(B1-Pad3.3V)") (class "Default")
      (node (ref "B1") (pin "3.3V") (pinfunction "3.3V_3.3V") (pintype "bidirectional"))
    )
    (net (code "90") (name "unconnected-(B1-Pad5V)") (class "Default")
      (node (ref "B1") (pin "5V") (pinfunction "5V_5V") (pintype "bidirectional"))
    )
    (net (code "91") (name "unconnected-(B1-PadA0)") (class "Default")
      (node (ref "B1") (pin "A0") (pinfunction "A0_A0") (pintype "bidirectional"))
    )
    (net (code "92") (name "unconnected-(B1-PadA1)") (class "Default")
      (node (ref "B1") (pin "A1") (pinfunction "A1_A1") (pintype "bidirectional"))
    )
    (net (code "93") (name "unconnected-(B1-PadA2)") (class "Default")
      (node (ref "B1") (pin "A2") (pinfunction "A2_A2") (pintype "bidirectional"))
    )
    (net (code "94") (name "unconnected-(B1-PadA3)") (class "Default")
      (node (ref "B1") (pin "A3") (pinfunction "A3_A3") (pintype "bidirectional"))
    )
    (net (code "95") (name "unconnected-(B1-PadA4)") (class "Default")
      (node (ref "B1") (pin "A4") (pinfunction "A4_A4") (pintype "bidirectional"))
    )
    (net (code "96") (name "unconnected-(B1-PadA5)") (class "Default")
      (node (ref "B1") (pin "A5") (pinfunction "A5_A5") (pintype "bidirectional"))
    )
    (net (code "97") (name "unconnected-(B1-PadAREF)") (class "Default")
      (node (ref "B1") (pin "AREF") (pinfunction "AREF_AREF") (pintype "bidirectional"))
    )
    (net (code "98") (name "unconnected-(B1-PadD0)") (class "Default")
      (node (ref "B1") (pin "D0") (pinfunction "D0_D0") (pintype "bidirectional"))
    )
    (net (code "99") (name "unconnected-(B1-PadD1)") (class "Default")
      (node (ref "B1") (pin "D1") (pinfunction "D1_D1") (pintype "bidirectional"))
    )
    (net (code "100") (name "unconnected-(B1-PadD2)") (class "Default")
      (node (ref "B1") (pin "D2") (pinfunction "D2_D2") (pintype "bidirectional"))
    )
    (net (code "101") (name "unconnected-(B1-PadD4)") (class "Default")
      (node (ref "B1") (pin "D4") (pinfunction "D4_D4") (pintype "bidirectional"))
    )
    (net (code "102") (name "unconnected-(B1-PadD7)") (class "Default")
      (node (ref "B1") (pin "D7") (pinfunction "D7_D7") (pintype "bidirectional"))
    )
    (net (code "103") (name "unconnected-(B1-PadD8)") (class "Default")
      (node (ref "B1") (pin "D8") (pinfunction "D8_D8") (pintype "bidirectional"))
    )
    (net (code "104") (name "unconnected-(B1-PadD12)") (class "Default")
      (node (ref "B1") (pin "D12") (pinfunction "D12_D12") (pintype "bidirectional"))
    )
    (net (code "105") (name "unconnected-(B1-PadD13)") (class "Default")
      (node (ref "B1") (pin "D13") (pinfunction "D13_D13") (pintype "bidirectional"))
    )
    (net (code "106") (name "unconnected-(B1-PadIOREF)") (class "Default")
      (node (ref "B1") (pin "IOREF") (pinfunction "IOREF_IOREF") (pintype "bidirectional"))
    )
    (net (code "107") (name "unconnected-(B1-PadMISO)") (class "Default")
      (node (ref "B1") (pin "MISO") (pinfunction "MISO_MISO") (pintype "bidirectional"))
    )
    (net (code "108") (name "unconnected-(B1-PadMOSI)") (class "Default")
      (node (ref "B1") (pin "MOSI") (pinfunction "MOSI_MOSI") (pintype "bidirectional"))
    )
    (net (code "109") (name "unconnected-(B1-PadSCK)") (class "Default")
      (node (ref "B1") (pin "SCK") (pinfunction "SCK_SCK") (pintype "bidirectional"))
    )
    (net (code "110") (name "unconnected-(B1-PadSCL)") (class "Default")
      (node (ref "B1") (pin "SCL") (pinfunction "SCL_SCL") (pintype "bidirectional"))
    )
    (net (code "111") (name "unconnected-(B1-PadSDA)") (class "Default")
      (node (ref "B1") (pin "SDA") (pinfunction "SDA_SDA") (pintype "bidirectional"))
    )
    (net (code "112") (name "unconnected-(B1-PadVCC)") (class "Default")
      (node (ref "B1") (pin "VCC") (pinfunction "VCC_VCC") (pintype "bidirectional"))
    )
    (net (code "113") (name "unconnected-(B1-PadVIN)") (class "Default")
      (node (ref "B1") (pin "VIN") (pinfunction "VIN_VIN") (pintype "bidirectional"))
    )
    (net (code "114") (name "unconnected-(B1-~{RESET}-PadRESET@1)") (class "Default")
      (node (ref "B1") (pin "RESET@1") (pinfunction "~{RESET}_RESET@1") (pintype "bidirectional"))
    )
    (net (code "115") (name "unconnected-(B1-~{RESET}-PadRESET@2)") (class "Default")
      (node (ref "B1") (pin "RESET@2") (pinfunction "~{RESET}_RESET@2") (pintype "bidirectional"))
    )
    (net (code "116") (name "unconnected-(J4-Pad1)") (class "Default")
      (node (ref "J4") (pin "1") (pinfunction "1_1") (pintype "passive"))
    )
    (net (code "117") (name "unconnected-(J4-Pad2)") (class "Default")
      (node (ref "J4") (pin "2") (pinfunction "2_2") (pintype "passive"))
    )
    (net (code "118") (name "unconnected-(J5-SBU1-PadA8)") (class "Default")
      (node (ref "J5") (pin "A8") (pinfunction "SBU1_A8") (pintype "bidirectional"))
    )
    (net (code "119") (name "unconnected-(J5-SBU2-PadB8)") (class "Default")
      (node (ref "J5") (pin "B8") (pinfunction "SBU2_B8") (pintype "bidirectional"))
    )
    (net (code "120") (name "unconnected-(TVS1-IO3-Pad4)") (class "Default")
      (node (ref "TVS1") (pin "4") (pinfunction "IO3_4") (pintype "passive"))
    )
    (net (code "121") (name "unconnected-(TVS1-IO4-Pad6)") (class "Default")
      (node (ref "TVS1") (pin "6") (pinfunction "IO4_6") (pintype "passive"))
    )
    (net (code "122") (name "unconnected-(U1-CLK-Pad20)") (class "Default")
      (node (ref "U1") (pin "20") (pinfunction "CLK_20") (pintype "bidirectional"))
    )
    (net (code "123") (name "unconnected-(U1-CMD-Pad19)") (class "Default")
      (node (ref "U1") (pin "19") (pinfunction "CMD_19") (pintype "bidirectional"))
    )
    (net (code "124") (name "unconnected-(U1-IO2-Pad24)") (class "Default")
      (node (ref "U1") (pin "24") (pinfunction "IO2_24") (pintype "bidirectional"))
    )
    (net (code "125") (name "unconnected-(U1-IO4-Pad26)") (class "Default")
      (node (ref "U1") (pin "26") (pinfunction "IO4_26") (pintype "bidirectional"))
    )
    (net (code "126") (name "unconnected-(U1-IO12-Pad14)") (class "Default")
      (node (ref "U1") (pin "14") (pinfunction "IO12_14") (pintype "bidirectional"))
    )
    (net (code "127") (name "unconnected-(U1-IO13-Pad16)") (class "Default")
      (node (ref "U1") (pin "16") (pinfunction "IO13_16") (pintype "bidirectional"))
    )
    (net (code "128") (name "unconnected-(U1-IO15-Pad23)") (class "Default")
      (node (ref "U1") (pin "23") (pinfunction "IO15_23") (pintype "bidirectional"))
    )
    (net (code "129") (name "unconnected-(U1-IO16-Pad27)") (class "Default")
      (node (ref "U1") (pin "27") (pinfunction "IO16_27") (pintype "bidirectional"))
    )
    (net (code "130") (name "unconnected-(U1-IO17-Pad28)") (class "Default")
      (node (ref "U1") (pin "28") (pinfunction "IO17_28") (pintype "bidirectional"))
    )
    (net (code "131") (name "unconnected-(U1-IO19-Pad31)") (class "Default")
      (node (ref "U1") (pin "31") (pinfunction "IO19_31") (pintype "bidirectional"))
    )
    (net (code "132") (name "unconnected-(U1-IO32-Pad8)") (class "Default")
      (node (ref "U1") (pin "8") (pinfunction "IO32_8") (pintype "bidirectional"))
    )
    (net (code "133") (name "unconnected-(U1-IO34-Pad6)") (class "Default")
      (node (ref "U1") (pin "6") (pinfunction "IO34_6") (pintype "bidirectional"))
    )
    (net (code "134") (name "unconnected-(U1-IO35-Pad7)") (class "Default")
      (node (ref "U1") (pin "7") (pinfunction "IO35_7") (pintype "bidirectional"))
    )
    (net (code "135") (name "unconnected-(U1-SD0-Pad21)") (class "Default")
      (node (ref "U1") (pin "21") (pinfunction "SD0_21") (pintype "bidirectional"))
    )
    (net (code "136") (name "unconnected-(U1-SD1-Pad22)") (class "Default")
      (node (ref "U1") (pin "22") (pinfunction "SD1_22") (pintype "bidirectional"))
    )
    (net (code "137") (name "unconnected-(U1-SD2-Pad17)") (class "Default")
      (node (ref "U1") (pin "17") (pinfunction "SD2_17") (pintype "bidirectional"))
    )
    (net (code "138") (name "unconnected-(U1-SD3-Pad18)") (class "Default")
      (node (ref "U1") (pin "18") (pinfunction "SD3_18") (pintype "bidirectional"))
    )
    (net (code "139") (name "unconnected-(U1-SVN-Pad5)") (class "Default")
      (node (ref "U1") (pin "5") (pinfunction "SVN_5") (pintype "bidirectional"))
    )
    (net (code "140") (name "unconnected-(U1-SVP-Pad4)") (class "Default")
      (node (ref "U1") (pin "4") (pinfunction "SVP_4") (pintype "bidirectional"))
    )
    (net (code "141") (name "unconnected-(U4-PA02-Pad18)") (class "Default")
      (node (ref "U4") (pin "18") (pinfunction "PA02_18") (pintype "bidirectional"))
    )
    (net (code "142") (name "unconnected-(U4-PA03-Pad19)") (class "Default")
      (node (ref "U4") (pin "19") (pinfunction "PA03_19") (pintype "bidirectional"))
    )
    (net (code "143") (name "unconnected-(U4-PA04-Pad20)") (class "Default")
      (node (ref "U4") (pin "20") (pinfunction "PA04_20") (pintype "bidirectional"))
    )
    (net (code "144") (name "unconnected-(U4-PA05-Pad1)") (class "Default")
      (node (ref "U4") (pin "1") (pinfunction "PA05_1") (pintype "bidirectional"))
    )
    (net (code "145") (name "unconnected-(U4-PA06-Pad2)") (class "Default")
      (node (ref "U4") (pin "2") (pinfunction "PA06_2") (pintype "bidirectional"))
    )
    (net (code "146") (name "unconnected-(U4-PA07-Pad3)") (class "Default")
      (node (ref "U4") (pin "3") (pinfunction "PA07_3") (pintype "bidirectional"))
    )
    (net (code "147") (name "unconnected-(U4-PA08{slash}XIN32-Pad4)") (class "Default")
      (node (ref "U4") (pin "4") (pinfunction "PA08/XIN32_4") (pintype "input"))
    )
    (net (code "148") (name "unconnected-(U4-PA09{slash}XOUT32-Pad5)") (class "Default")
      (node (ref "U4") (pin "5") (pinfunction "PA09/XOUT32_5") (pintype "input"))
    )
    (net (code "149") (name "unconnected-(U4-PA16-Pad8)") (class "Default")
      (node (ref "U4") (pin "8") (pinfunction "PA16_8") (pintype "bidirectional"))
    )
    (net (code "150") (name "unconnected-(U6-4A-Pad9)") (class "Default")
      (node (ref "U6") (pin "9") (pinfunction "4A_9") (pintype "bidirectional"))
    )
    (net (code "151") (name "unconnected-(U6-4Y-Pad10)") (class "Default")
      (node (ref "U6") (pin "10") (pinfunction "4Y_10") (pintype "bidirectional"))
    )
  )
)
